# Production_SmartMic_V01.net
KiCad netlist of a schematic drawn in EAGLE
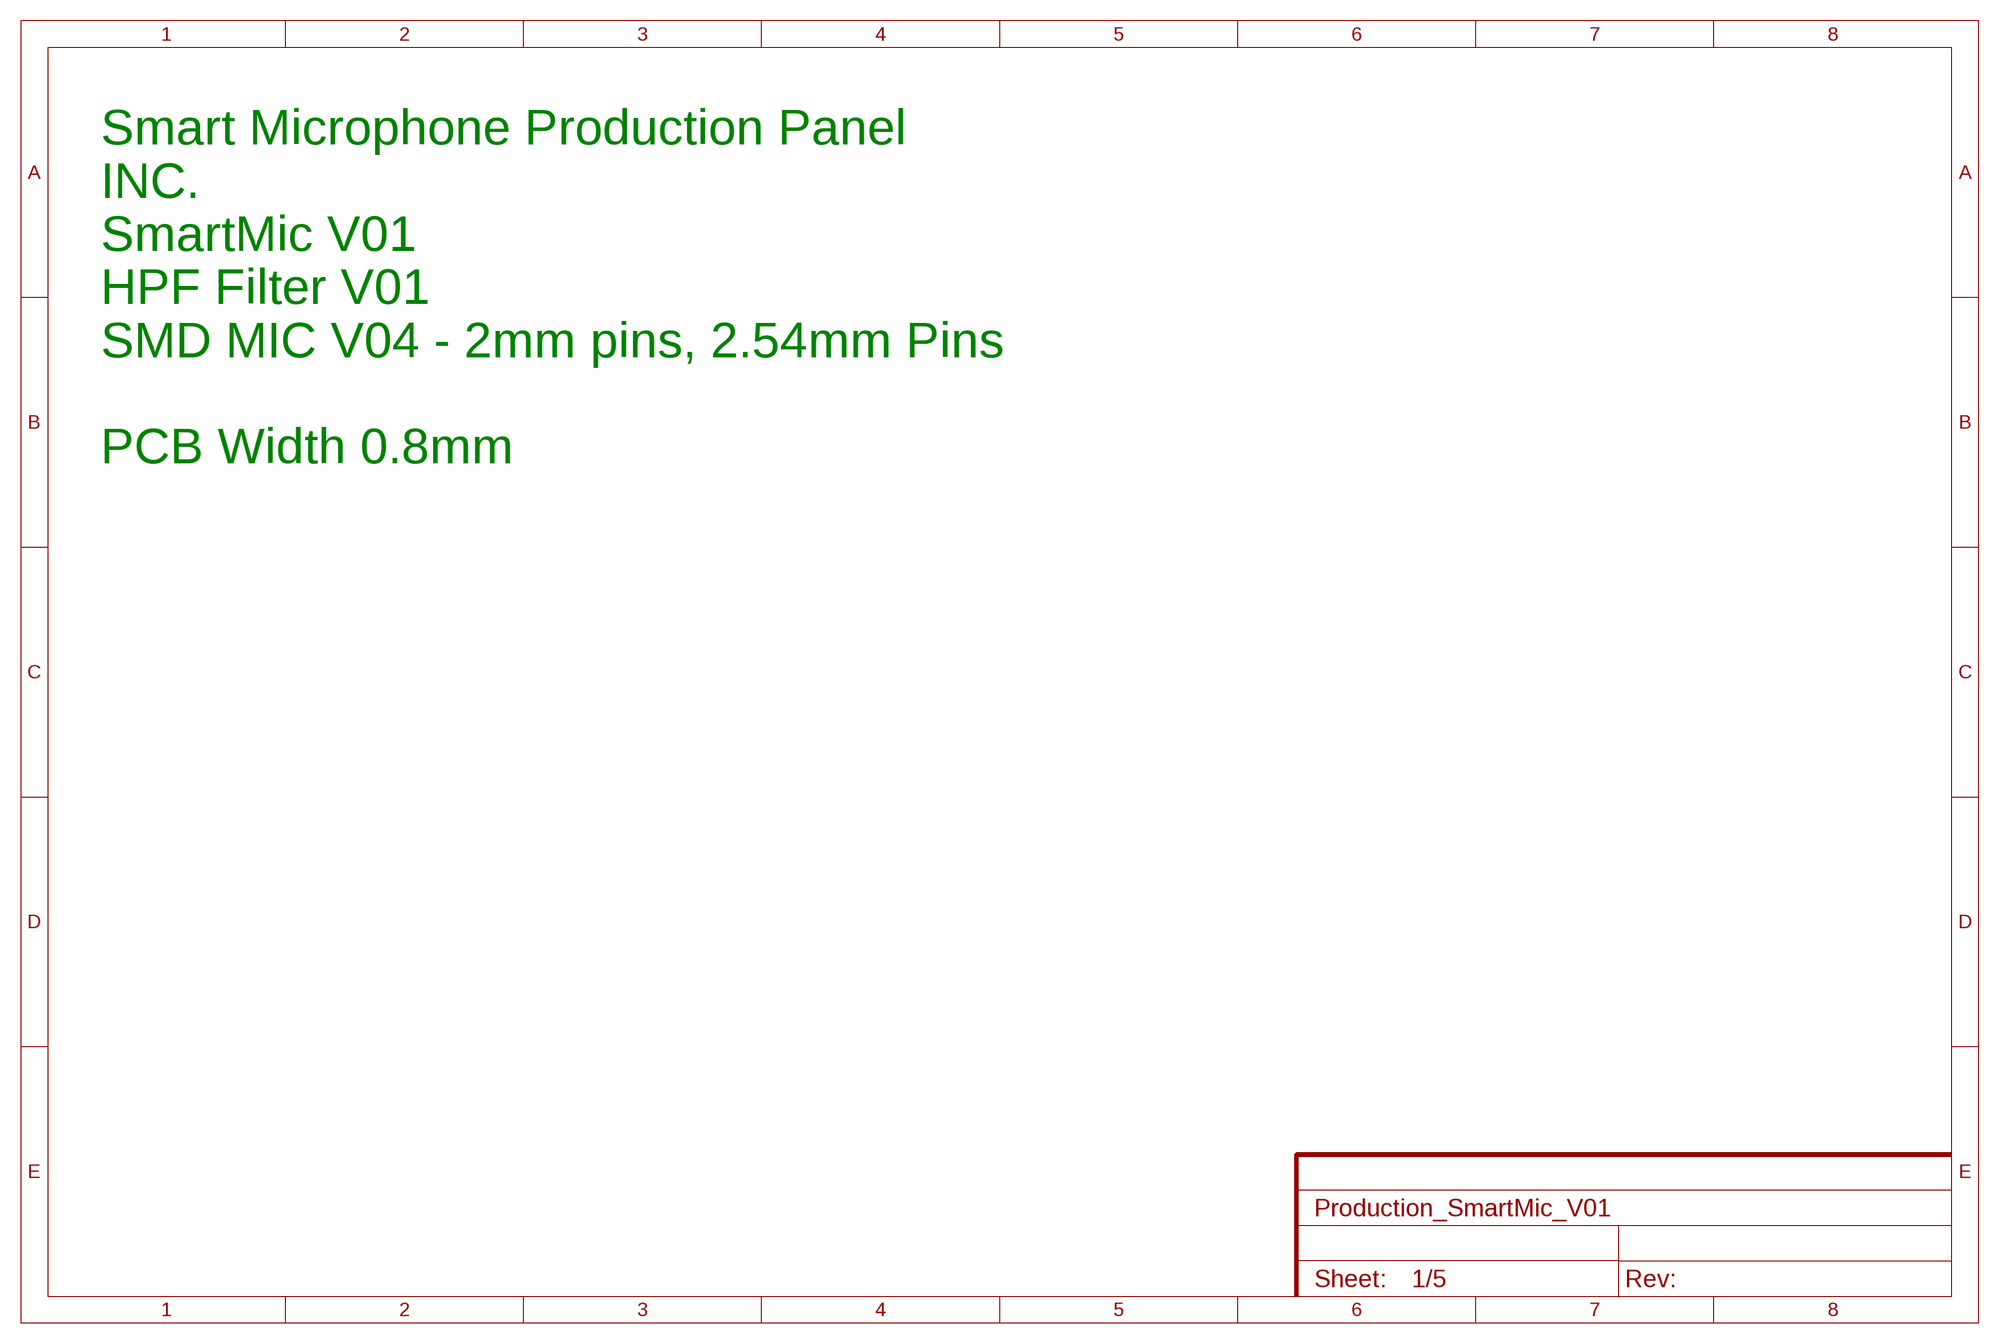
[diagram p0: schematic, sheet 1]
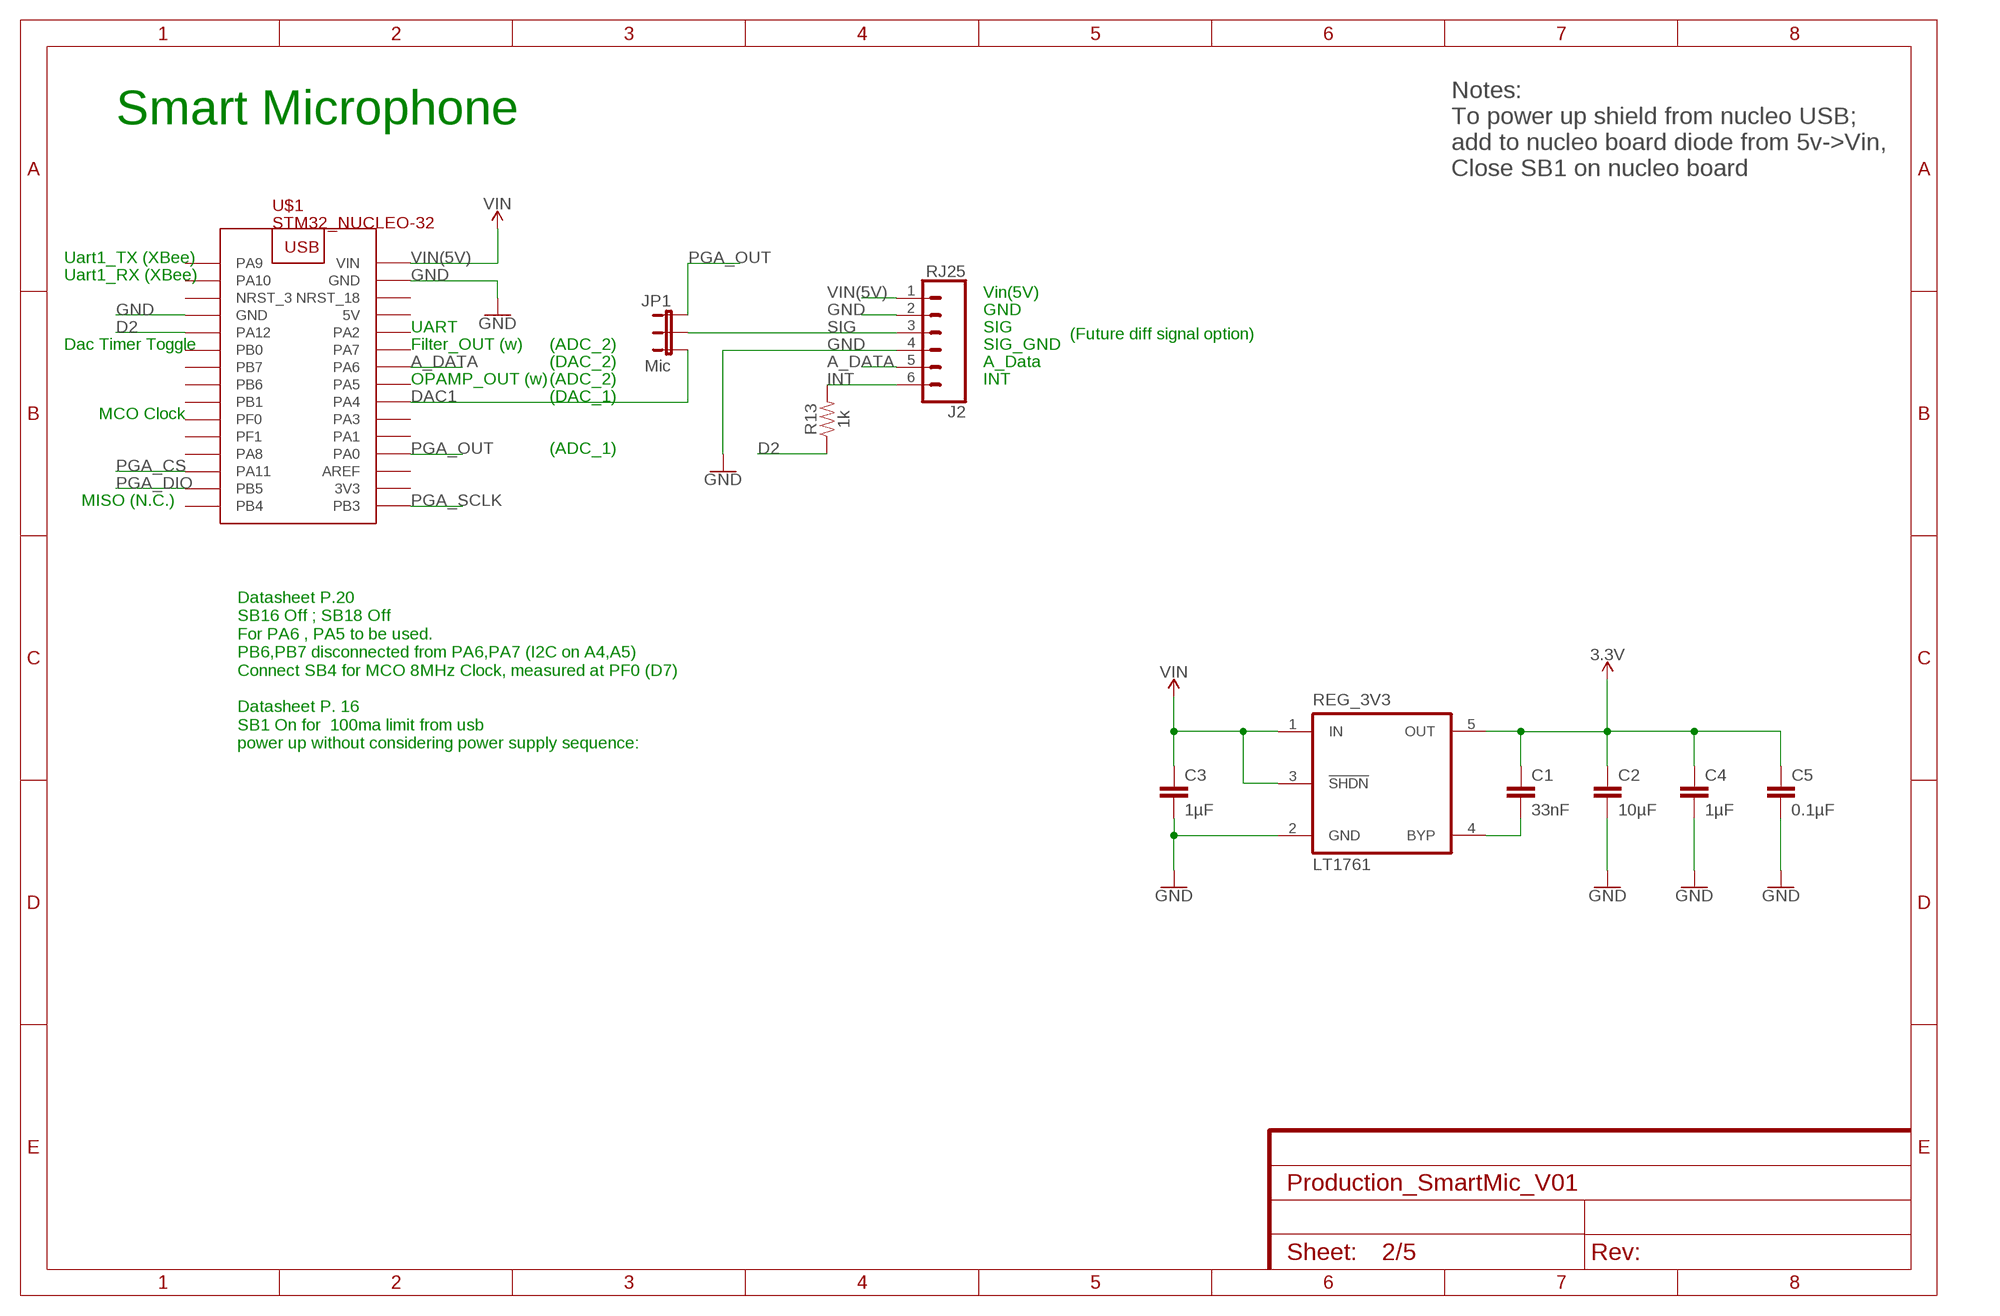
[diagram p1: schematic, sheet 2]
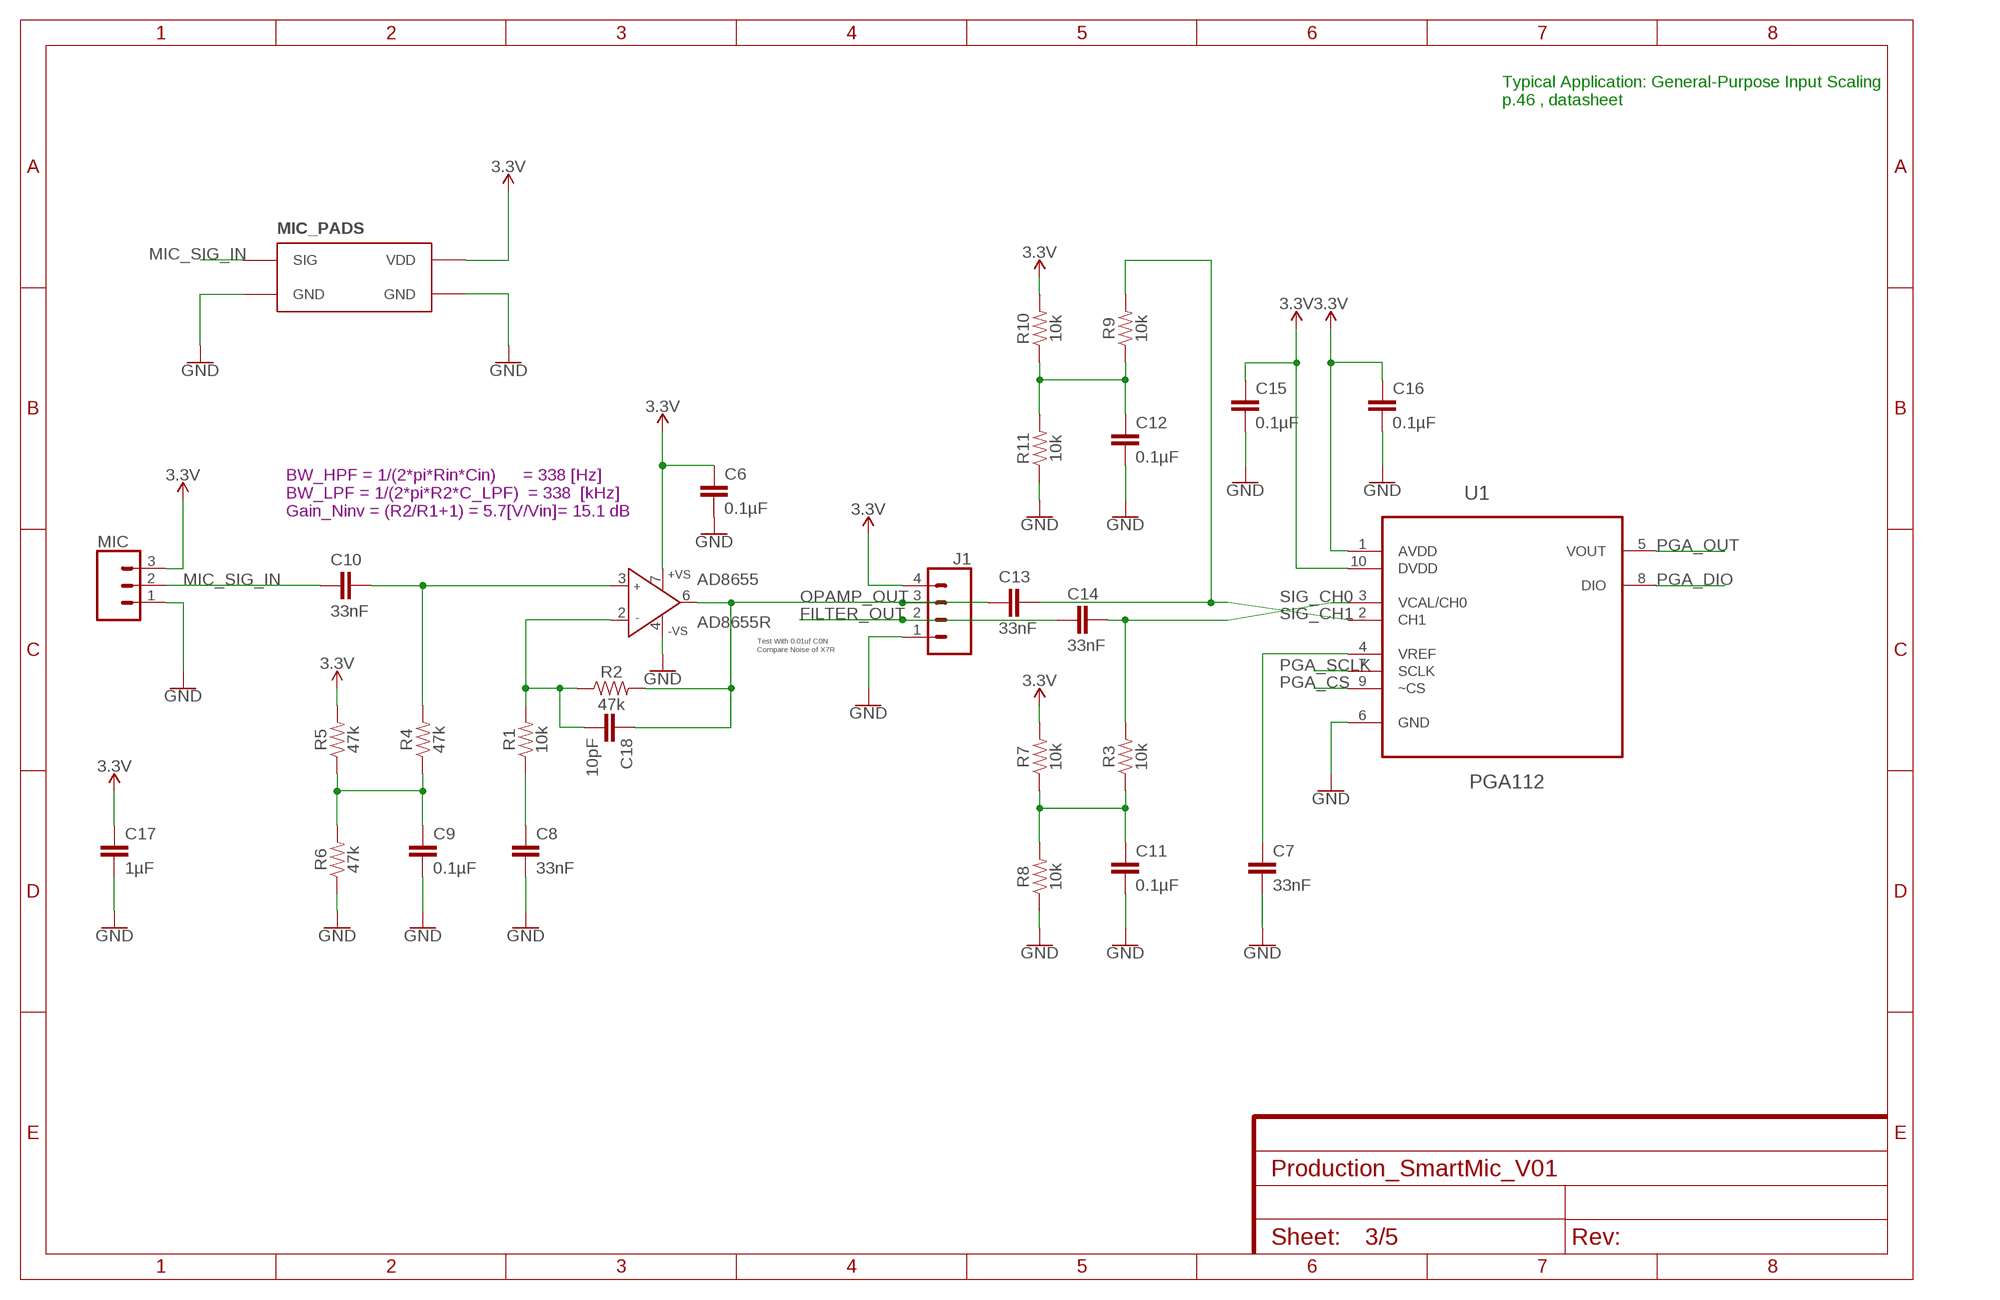
[diagram p2: schematic, sheet 3]
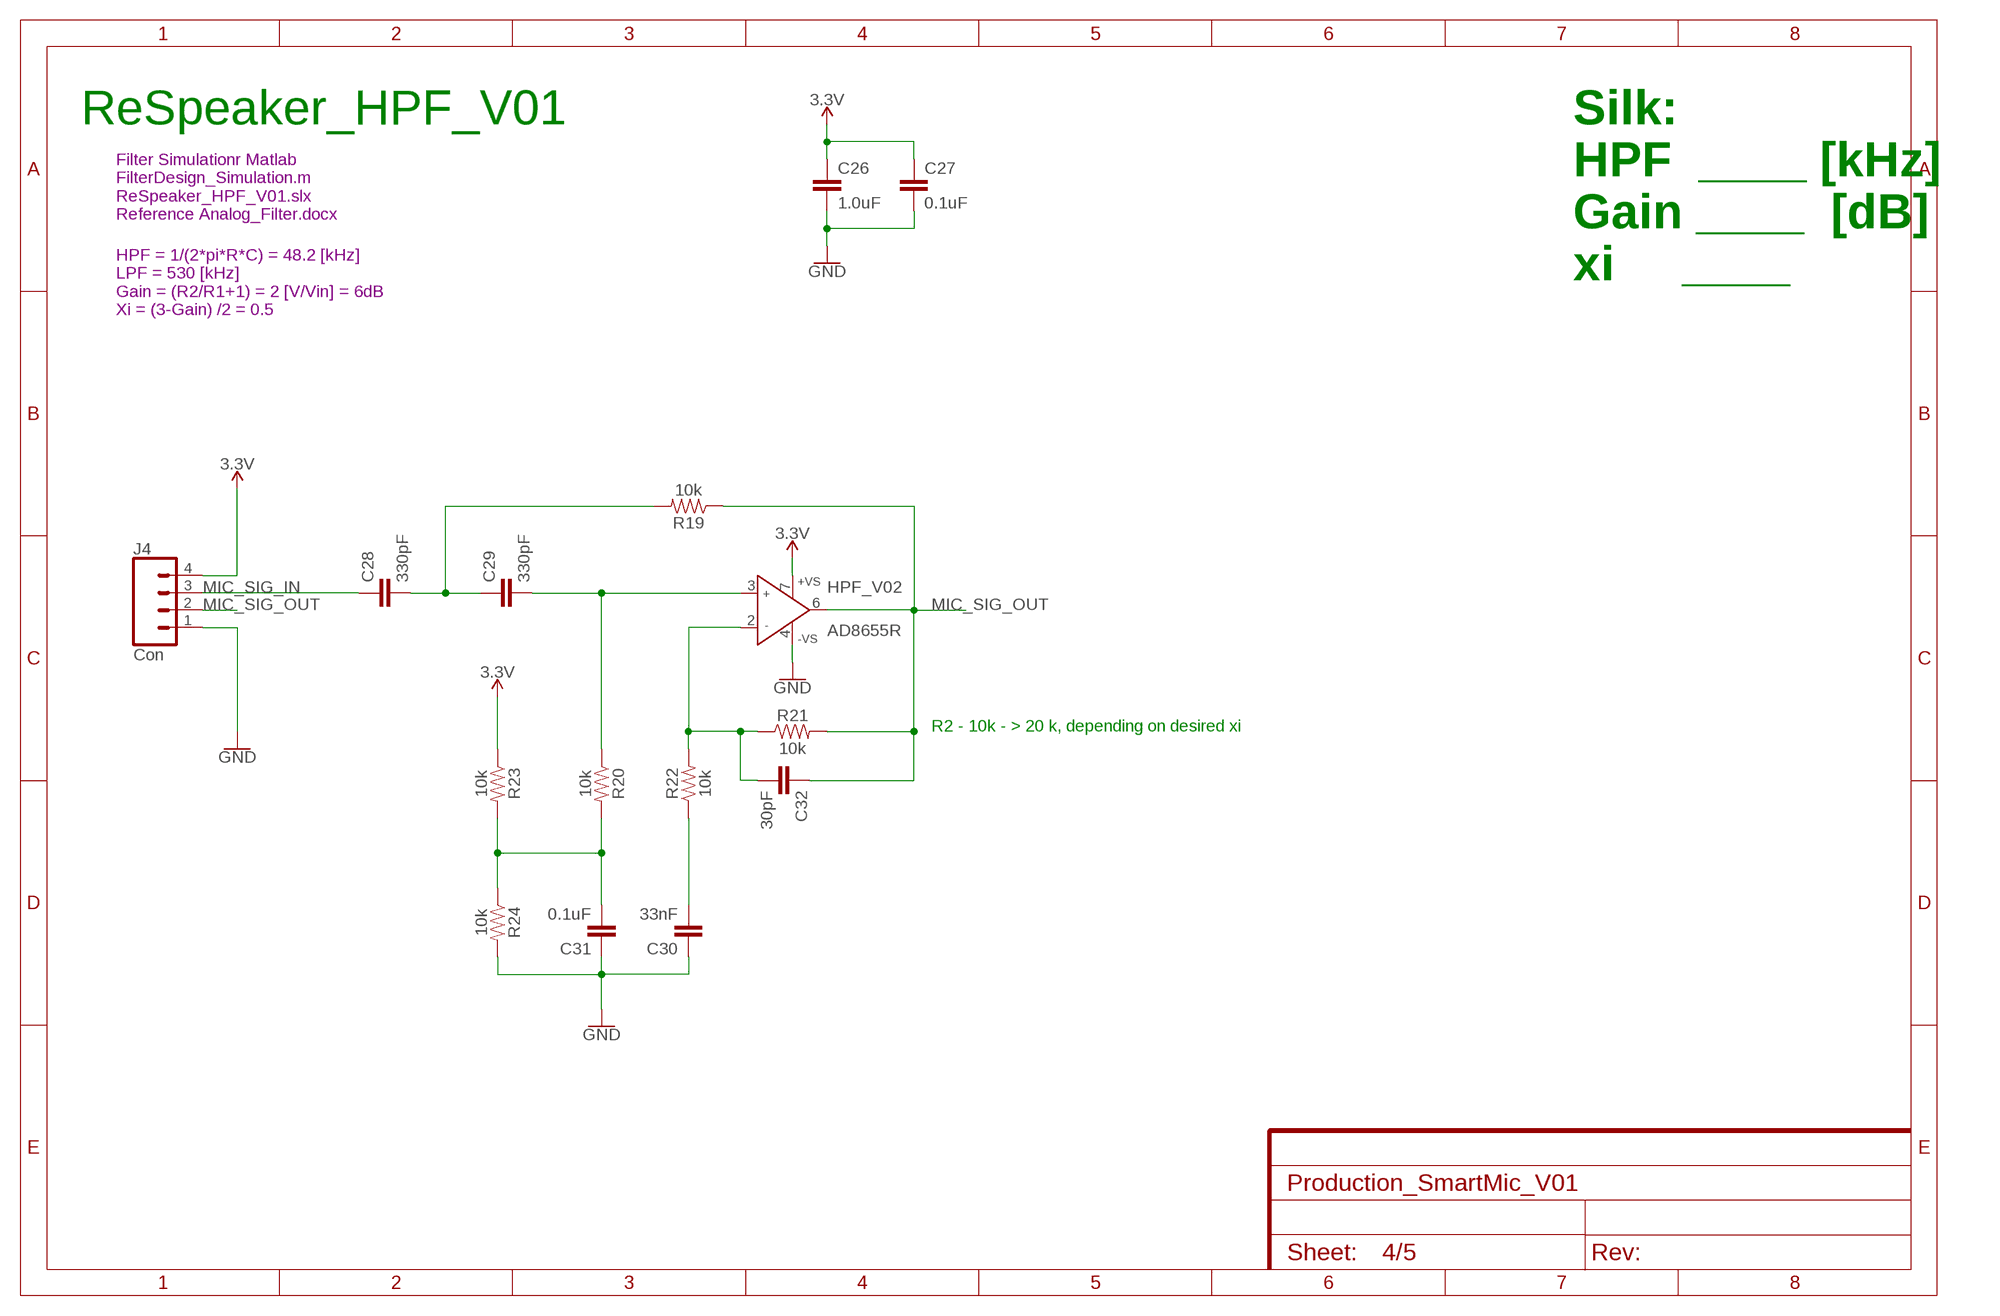
[diagram p3: schematic, sheet 4]
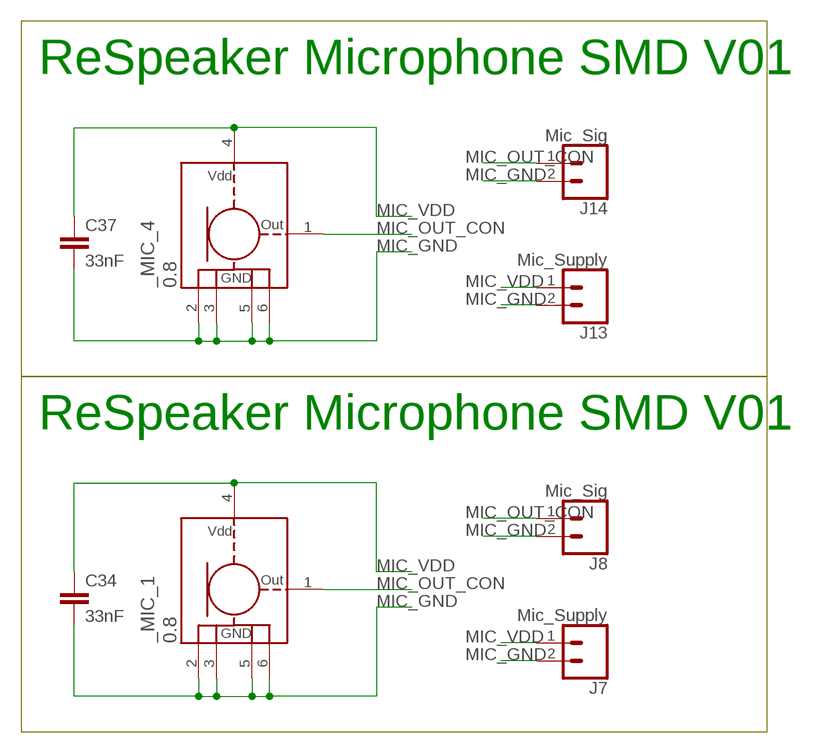
[diagram p4: schematic, sheet 5]

(export (version "E")
  (design (tool "Eeschema 10.0.6"))
  (components
    (comp (ref "C1")
      (value "33nF")
      (footprint "eagle-import:0805")
      (libsource (lib "eagle-import") (part "0.33UF/330NF-0805-50V-10%"))
    )
    (comp (ref "C2")
      (value "10µF")
      (footprint "eagle-import:0805")
      (libsource (lib "eagle-import") (part "0.33UF/330NF-0805-50V-10%"))
    )
    (comp (ref "C3")
      (value "1µF")
      (footprint "eagle-import:0805")
      (libsource (lib "eagle-import") (part "0.33UF/330NF-0805-50V-10%"))
    )
    (comp (ref "C4")
      (value "1µF")
      (footprint "eagle-import:0805")
      (libsource (lib "eagle-import") (part "0.33UF/330NF-0805-50V-10%"))
    )
    (comp (ref "C5")
      (value "0.1µF")
      (footprint "eagle-import:0805")
      (libsource (lib "eagle-import") (part "0.33UF/330NF-0805-50V-10%"))
    )
    (comp (ref "J2")
      (value "RJ25")
      (footprint "eagle-import:RJ11-6")
      (libsource (lib "eagle-import") (part "RJ11-6"))
    )
    (comp (ref "JP1")
      (value "Mic")
      (footprint "eagle-import:1X03")
      (libsource (lib "eagle-import") (part "JUMPER-3PTH"))
    )
    (comp (ref "R13")
      (value "1k")
      (footprint "eagle-import:0805")
      (libsource (lib "eagle-import") (part "RESISTOR0805"))
    )
    (comp (ref "REG_3V3")
      (value "LT1761")
      (footprint "eagle-import:SOT23-5")
      (libsource (lib "eagle-import") (part "LT1761"))
    )
    (comp (ref "U$1")
      (value "STM32_NUCLEO-32")
      (footprint "eagle-import:STM32_NUCLEO-32")
      (libsource (lib "eagle-import") (part "STM32_NUCLEO-32"))
    )
    (comp (ref "C26")
      (value "1.0uF")
      (footprint "eagle-import:0805")
      (libsource (lib "eagle-import") (part "1.0UF-0805-25V-10%"))
    )
    (comp (ref "C27")
      (value "0.1uF")
      (footprint "eagle-import:0805")
      (libsource (lib "eagle-import") (part "1.0UF-0805-25V-10%"))
    )
    (comp (ref "C28")
      (value "330pF")
      (footprint "eagle-import:0805")
      (libsource (lib "eagle-import") (part "1.0UF-0805-25V-10%"))
    )
    (comp (ref "C29")
      (value "330pF")
      (footprint "eagle-import:0805")
      (libsource (lib "eagle-import") (part "1.0UF-0805-25V-10%"))
    )
    (comp (ref "C30")
      (value "33nF")
      (footprint "eagle-import:0805")
      (libsource (lib "eagle-import") (part "1.0UF-0805-25V-10%"))
    )
    (comp (ref "C31")
      (value "0.1uF")
      (footprint "eagle-import:0805")
      (libsource (lib "eagle-import") (part "1.0UF-0805-25V-10%"))
    )
    (comp (ref "C32")
      (value "30pF")
      (footprint "eagle-import:0805")
      (libsource (lib "eagle-import") (part "1.0UF-0805-25V-10%"))
    )
    (comp (ref "HPF_V02")
      (value "AD8655R")
      (footprint "eagle-import:SO8")
      (fields (field (name "MF") "ALTERA CORPORATION") (field (name "MPN") "AD8655ARMZ-REEL"))
      (libsource (lib "eagle-import") (part "AD8655R"))
    )
    (comp (ref "J4")
      (value "Con")
      (footprint "eagle-import:1X04")
      (libsource (lib "eagle-import") (part "CONN_04"))
    )
    (comp (ref "R19")
      (value "10k")
      (footprint "eagle-import:0805")
      (libsource (lib "eagle-import") (part "RESISTOR0805"))
    )
    (comp (ref "R20")
      (value "10k")
      (footprint "eagle-import:0805")
      (libsource (lib "eagle-import") (part "RESISTOR0805"))
    )
    (comp (ref "R21")
      (value "10k")
      (footprint "eagle-import:0805")
      (libsource (lib "eagle-import") (part "RESISTOR0805"))
    )
    (comp (ref "R22")
      (value "10k")
      (footprint "eagle-import:0805")
      (libsource (lib "eagle-import") (part "RESISTOR0805"))
    )
    (comp (ref "R23")
      (value "10k")
      (footprint "eagle-import:0805")
      (libsource (lib "eagle-import") (part "RESISTOR0805"))
    )
    (comp (ref "R24")
      (value "10k")
      (footprint "eagle-import:0805")
      (libsource (lib "eagle-import") (part "RESISTOR0805"))
    )
    (comp (ref "C34")
      (value "33nF")
      (footprint "eagle-import:0805")
      (libsource (lib "eagle-import") (part "1.0UF-0805-25V-10%"))
    )
    (comp (ref "C37")
      (value "33nF")
      (footprint "eagle-import:0805")
      (libsource (lib "eagle-import") (part "1.0UF-0805-25V-10%"))
    )
    (comp (ref "J7")
      (value "Mic_Supply")
      (footprint "eagle-import:1X02_2.0MM")
      (libsource (lib "eagle-import") (part "CONN_021X02_2MM"))
    )
    (comp (ref "J8")
      (value "Mic_Sig")
      (footprint "eagle-import:1X02_2.0MM")
      (libsource (lib "eagle-import") (part "CONN_021X02_2MM"))
    )
    (comp (ref "J13")
      (value "Mic_Supply")
      (footprint "eagle-import:1X02")
      (libsource (lib "eagle-import") (part "SparkFun-Connectors_CONN_02"))
    )
    (comp (ref "J14")
      (value "Mic_Sig")
      (footprint "eagle-import:1X02")
      (libsource (lib "eagle-import") (part "SparkFun-Connectors_CONN_02"))
    )
    (comp (ref "_MIC_1")
      (value "0.8")
      (footprint "eagle-import:SPU0410LR5H-QB_0.8")
      (libsource (lib "eagle-import") (part "SPU0410LR5H-QBSPU0410LR5H-QB_0.8"))
    )
    (comp (ref "_MIC_4")
      (value "0.8")
      (footprint "eagle-import:SPU0410LR5H-QB_0.8")
      (libsource (lib "eagle-import") (part "SPU0410LR5H-QBSPU0410LR5H-QB_0.8"))
    )
    (comp (ref "AD8655")
      (value "AD8655R")
      (footprint "eagle-import:SO8")
      (fields (field (name "MF") "ALTERA CORPORATION") (field (name "MPN") "AD8655ARMZ-REEL"))
      (libsource (lib "eagle-import") (part "AD8655R"))
    )
    (comp (ref "C6")
      (value "0.1µF")
      (footprint "eagle-import:0805")
      (libsource (lib "eagle-import") (part "0.33UF/330NF-0805-50V-10%"))
    )
    (comp (ref "C7")
      (value "33nF")
      (footprint "eagle-import:0805")
      (libsource (lib "eagle-import") (part "0.33UF/330NF-0805-50V-10%"))
    )
    (comp (ref "C8")
      (value "33nF")
      (footprint "eagle-import:0805")
      (libsource (lib "eagle-import") (part "0.33UF/330NF-0805-50V-10%"))
    )
    (comp (ref "C9")
      (value "0.1µF")
      (footprint "eagle-import:0805")
      (libsource (lib "eagle-import") (part "0.33UF/330NF-0805-50V-10%"))
    )
    (comp (ref "C10")
      (value "33nF")
      (footprint "eagle-import:0805")
      (libsource (lib "eagle-import") (part "0.33UF/330NF-0805-50V-10%"))
    )
    (comp (ref "C11")
      (value "0.1µF")
      (footprint "eagle-import:0805")
      (libsource (lib "eagle-import") (part "0.33UF/330NF-0805-50V-10%"))
    )
    (comp (ref "C12")
      (value "0.1µF")
      (footprint "eagle-import:0805")
      (libsource (lib "eagle-import") (part "0.33UF/330NF-0805-50V-10%"))
    )
    (comp (ref "C13")
      (value "33nF")
      (footprint "eagle-import:0805")
      (libsource (lib "eagle-import") (part "0.33UF/330NF-0805-50V-10%"))
    )
    (comp (ref "C14")
      (value "33nF")
      (footprint "eagle-import:0805")
      (libsource (lib "eagle-import") (part "0.33UF/330NF-0805-50V-10%"))
    )
    (comp (ref "C15")
      (value "0.1µF")
      (footprint "eagle-import:0805")
      (libsource (lib "eagle-import") (part "0.33UF/330NF-0805-50V-10%"))
    )
    (comp (ref "C16")
      (value "0.1µF")
      (footprint "eagle-import:0805")
      (libsource (lib "eagle-import") (part "0.33UF/330NF-0805-50V-10%"))
    )
    (comp (ref "C17")
      (value "1µF")
      (footprint "eagle-import:0805")
      (libsource (lib "eagle-import") (part "0.33UF/330NF-0805-50V-10%"))
    )
    (comp (ref "C18")
      (value "10pF")
      (footprint "eagle-import:0805")
      (libsource (lib "eagle-import") (part "0.33UF/330NF-0805-50V-10%"))
    )
    (comp (ref "J1")
      (value "CONN_04")
      (footprint "eagle-import:1X04")
      (libsource (lib "eagle-import") (part "CONN_04"))
    )
    (comp (ref "MIC")
      (value "CONN_03")
      (footprint "eagle-import:1X03")
      (libsource (lib "eagle-import") (part "CONN_03"))
    )
    (comp (ref "R1")
      (value "10k")
      (footprint "eagle-import:0805")
      (libsource (lib "eagle-import") (part "RESISTOR0805"))
    )
    (comp (ref "R2")
      (value "47k")
      (footprint "eagle-import:0805")
      (libsource (lib "eagle-import") (part "RESISTOR0805"))
    )
    (comp (ref "R3")
      (value "10k")
      (footprint "eagle-import:0805")
      (libsource (lib "eagle-import") (part "RESISTOR0805"))
    )
    (comp (ref "R4")
      (value "47k")
      (footprint "eagle-import:0805")
      (libsource (lib "eagle-import") (part "RESISTOR0805"))
    )
    (comp (ref "R5")
      (value "47k")
      (footprint "eagle-import:0805")
      (libsource (lib "eagle-import") (part "RESISTOR0805"))
    )
    (comp (ref "R6")
      (value "47k")
      (footprint "eagle-import:0805")
      (libsource (lib "eagle-import") (part "RESISTOR0805"))
    )
    (comp (ref "R7")
      (value "10k")
      (footprint "eagle-import:0805")
      (libsource (lib "eagle-import") (part "RESISTOR0805"))
    )
    (comp (ref "R8")
      (value "10k")
      (footprint "eagle-import:0805")
      (libsource (lib "eagle-import") (part "RESISTOR0805"))
    )
    (comp (ref "R9")
      (value "10k")
      (footprint "eagle-import:0805")
      (libsource (lib "eagle-import") (part "RESISTOR0805"))
    )
    (comp (ref "R10")
      (value "10k")
      (footprint "eagle-import:0805")
      (libsource (lib "eagle-import") (part "RESISTOR0805"))
    )
    (comp (ref "R11")
      (value "10k")
      (footprint "eagle-import:0805")
      (libsource (lib "eagle-import") (part "RESISTOR0805"))
    )
    (comp (ref "U$2")
      (value "MIC_PADS")
      (footprint "eagle-import:MIC_PADS")
      (libsource (lib "eagle-import") (part "MIC_PADS"))
    )
    (comp (ref "U1")
      (value "PGA112")
      (footprint "eagle-import:SOP50P490X110-10N")
      (fields (field (name "MPN") "PGA113AIDGST"))
      (libsource (lib "eagle-import") (part "PGA113AIDGST"))
    )
  )
  (nets
    (net (code "1") (name "3.3V") (class "Default")
      (node (ref "AD8655") (pin "7") (pinfunction "+VS_7") (pintype "input"))
      (node (ref "C1") (pin "1") (pinfunction "1_1") (pintype "passive"))
      (node (ref "C15") (pin "1") (pinfunction "1_1") (pintype "passive"))
      (node (ref "C16") (pin "1") (pinfunction "1_1") (pintype "passive"))
      (node (ref "C17") (pin "1") (pinfunction "1_1") (pintype "passive"))
      (node (ref "C2") (pin "1") (pinfunction "1_1") (pintype "passive"))
      (node (ref "C26") (pin "1") (pinfunction "1_1") (pintype "passive"))
      (node (ref "C27") (pin "1") (pinfunction "1_1") (pintype "passive"))
      (node (ref "C4") (pin "1") (pinfunction "1_1") (pintype "passive"))
      (node (ref "C5") (pin "1") (pinfunction "1_1") (pintype "passive"))
      (node (ref "C6") (pin "1") (pinfunction "1_1") (pintype "passive"))
      (node (ref "HPF_V02") (pin "7") (pinfunction "+VS_7") (pintype "input"))
      (node (ref "J1") (pin "4") (pinfunction "4_4") (pintype "passive"))
      (node (ref "J4") (pin "4") (pinfunction "4_4") (pintype "passive"))
      (node (ref "MIC") (pin "3") (pinfunction "3_3") (pintype "passive"))
      (node (ref "R10") (pin "2") (pinfunction "2_2") (pintype "passive"))
      (node (ref "R23") (pin "1") (pinfunction "1_1") (pintype "passive"))
      (node (ref "R5") (pin "2") (pinfunction "2_2") (pintype "passive"))
      (node (ref "R7") (pin "2") (pinfunction "2_2") (pintype "passive"))
      (node (ref "REG_3V3") (pin "5") (pinfunction "OUT_5") (pintype "bidirectional"))
      (node (ref "U$2") (pin "VDD") (pinfunction "VDD_VDD") (pintype "bidirectional"))
      (node (ref "U1") (pin "1") (pinfunction "AVDD_1") (pintype "power_in"))
      (node (ref "U1") (pin "10") (pinfunction "DVDD_10") (pintype "power_in"))
    )
    (net (code "2") (name "3V3") (class "Default")
      (node (ref "U$1") (pin "3V3") (pinfunction "3V3_3V3") (pintype "power_in"))
    )
    (net (code "3") (name "5V") (class "Default")
      (node (ref "U$1") (pin "5V") (pinfunction "5V_5V") (pintype "power_in"))
    )
    (net (code "4") (name "A_DATA") (class "Default")
      (node (ref "J2") (pin "5") (pinfunction "5_5") (pintype "passive"))
      (node (ref "U$1") (pin "PA6") (pinfunction "PA6_PA6") (pintype "bidirectional"))
    )
    (net (code "5") (name "D2") (class "Default")
      (node (ref "R13") (pin "1") (pinfunction "1_1") (pintype "passive"))
      (node (ref "U$1") (pin "PA12") (pinfunction "PA12_PA12") (pintype "bidirectional"))
    )
    (net (code "6") (name "DAC1") (class "Default")
      (node (ref "JP1") (pin "3") (pinfunction "3_3") (pintype "passive"))
      (node (ref "U$1") (pin "PA4") (pinfunction "PA4_PA4") (pintype "bidirectional"))
    )
    (net (code "7") (name "FILTER_OUT") (class "Default")
      (node (ref "C14") (pin "2") (pinfunction "2_2") (pintype "passive"))
      (node (ref "J1") (pin "2") (pinfunction "2_2") (pintype "passive"))
    )
    (net (code "8") (name "GND") (class "Default")
      (node (ref "AD8655") (pin "4") (pinfunction "-VS_4") (pintype "input"))
      (node (ref "C11") (pin "2") (pinfunction "2_2") (pintype "passive"))
      (node (ref "C12") (pin "2") (pinfunction "2_2") (pintype "passive"))
      (node (ref "C15") (pin "2") (pinfunction "2_2") (pintype "passive"))
      (node (ref "C16") (pin "2") (pinfunction "2_2") (pintype "passive"))
      (node (ref "C17") (pin "2") (pinfunction "2_2") (pintype "passive"))
      (node (ref "C2") (pin "2") (pinfunction "2_2") (pintype "passive"))
      (node (ref "C26") (pin "2") (pinfunction "2_2") (pintype "passive"))
      (node (ref "C27") (pin "2") (pinfunction "2_2") (pintype "passive"))
      (node (ref "C3") (pin "2") (pinfunction "2_2") (pintype "passive"))
      (node (ref "C30") (pin "1") (pinfunction "1_1") (pintype "passive"))
      (node (ref "C31") (pin "1") (pinfunction "1_1") (pintype "passive"))
      (node (ref "C4") (pin "2") (pinfunction "2_2") (pintype "passive"))
      (node (ref "C5") (pin "2") (pinfunction "2_2") (pintype "passive"))
      (node (ref "C6") (pin "2") (pinfunction "2_2") (pintype "passive"))
      (node (ref "C7") (pin "2") (pinfunction "2_2") (pintype "passive"))
      (node (ref "C8") (pin "2") (pinfunction "2_2") (pintype "passive"))
      (node (ref "C9") (pin "2") (pinfunction "2_2") (pintype "passive"))
      (node (ref "HPF_V02") (pin "4") (pinfunction "-VS_4") (pintype "input"))
      (node (ref "J1") (pin "1") (pinfunction "1_1") (pintype "passive"))
      (node (ref "J2") (pin "2") (pinfunction "2_2") (pintype "passive"))
      (node (ref "J2") (pin "4") (pinfunction "4_4") (pintype "passive"))
      (node (ref "J4") (pin "1") (pinfunction "1_1") (pintype "passive"))
      (node (ref "MIC") (pin "1") (pinfunction "1_1") (pintype "passive"))
      (node (ref "R11") (pin "1") (pinfunction "1_1") (pintype "passive"))
      (node (ref "R24") (pin "2") (pinfunction "2_2") (pintype "passive"))
      (node (ref "R6") (pin "1") (pinfunction "1_1") (pintype "passive"))
      (node (ref "R8") (pin "1") (pinfunction "1_1") (pintype "passive"))
      (node (ref "REG_3V3") (pin "2") (pinfunction "GND_2") (pintype "bidirectional"))
      (node (ref "U$1") (pin "GND@17") (pinfunction "GND_GND@17") (pintype "power_in"))
      (node (ref "U$1") (pin "GND@4") (pinfunction "GND_GND@4") (pintype "power_in"))
      (node (ref "U$2") (pin "GND$2") (pinfunction "GND_GND$2") (pintype "bidirectional"))
      (node (ref "U$2") (pin "GND$4") (pinfunction "GND_GND$4") (pintype "bidirectional"))
      (node (ref "U1") (pin "6") (pinfunction "GND_6") (pintype "passive"))
    )
    (net (code "9") (name "INT") (class "Default")
      (node (ref "J2") (pin "6") (pinfunction "6_6") (pintype "passive"))
      (node (ref "R13") (pin "2") (pinfunction "2_2") (pintype "passive"))
    )
    (net (code "10") (name "MIC_GND") (class "Default")
      (node (ref "C34") (pin "2") (pinfunction "2_2") (pintype "passive"))
      (node (ref "C37") (pin "2") (pinfunction "2_2") (pintype "passive"))
      (node (ref "J13") (pin "2") (pinfunction "2_2") (pintype "passive"))
      (node (ref "J14") (pin "2") (pinfunction "2_2") (pintype "passive"))
      (node (ref "J7") (pin "2") (pinfunction "2_2") (pintype "passive"))
      (node (ref "J8") (pin "2") (pinfunction "2_2") (pintype "passive"))
      (node (ref "_MIC_1") (pin "2") (pinfunction "GND_2") (pintype "bidirectional"))
      (node (ref "_MIC_1") (pin "3") (pinfunction "GND_3") (pintype "bidirectional"))
      (node (ref "_MIC_1") (pin "5") (pinfunction "GND_5") (pintype "bidirectional"))
      (node (ref "_MIC_1") (pin "6") (pinfunction "GND_6") (pintype "bidirectional"))
      (node (ref "_MIC_4") (pin "2") (pinfunction "GND_2") (pintype "bidirectional"))
      (node (ref "_MIC_4") (pin "3") (pinfunction "GND_3") (pintype "bidirectional"))
      (node (ref "_MIC_4") (pin "5") (pinfunction "GND_5") (pintype "bidirectional"))
      (node (ref "_MIC_4") (pin "6") (pinfunction "GND_6") (pintype "bidirectional"))
    )
    (net (code "11") (name "MIC_OUT_CON") (class "Default")
      (node (ref "J14") (pin "1") (pinfunction "1_1") (pintype "passive"))
      (node (ref "J8") (pin "1") (pinfunction "1_1") (pintype "passive"))
      (node (ref "_MIC_1") (pin "1") (pinfunction "OUT_1") (pintype "bidirectional"))
      (node (ref "_MIC_4") (pin "1") (pinfunction "OUT_1") (pintype "bidirectional"))
    )
    (net (code "12") (name "MIC_SIG_IN") (class "Default")
      (node (ref "C10") (pin "2") (pinfunction "2_2") (pintype "passive"))
      (node (ref "C28") (pin "1") (pinfunction "1_1") (pintype "passive"))
      (node (ref "J4") (pin "3") (pinfunction "3_3") (pintype "passive"))
      (node (ref "MIC") (pin "2") (pinfunction "2_2") (pintype "passive"))
      (node (ref "U$2") (pin "SIG") (pinfunction "SIG_SIG") (pintype "bidirectional"))
    )
    (net (code "13") (name "MIC_SIG_OUT") (class "Default")
      (node (ref "C32") (pin "1") (pinfunction "1_1") (pintype "passive"))
      (node (ref "HPF_V02") (pin "6") (pinfunction "OUT_6") (pintype "output"))
      (node (ref "J4") (pin "2") (pinfunction "2_2") (pintype "passive"))
      (node (ref "R19") (pin "1") (pinfunction "1_1") (pintype "passive"))
      (node (ref "R21") (pin "2") (pinfunction "2_2") (pintype "passive"))
    )
    (net (code "14") (name "MIC_VDD") (class "Default")
      (node (ref "C34") (pin "1") (pinfunction "1_1") (pintype "passive"))
      (node (ref "C37") (pin "1") (pinfunction "1_1") (pintype "passive"))
      (node (ref "J13") (pin "1") (pinfunction "1_1") (pintype "passive"))
      (node (ref "J7") (pin "1") (pinfunction "1_1") (pintype "passive"))
      (node (ref "_MIC_1") (pin "4") (pinfunction "VDD_4") (pintype "bidirectional"))
      (node (ref "_MIC_4") (pin "4") (pinfunction "VDD_4") (pintype "bidirectional"))
    )
    (net (code "15") (name "Net-(AD8655-IN+)") (class "Default")
      (node (ref "AD8655") (pin "3") (pinfunction "IN+_3") (pintype "input"))
      (node (ref "C10") (pin "1") (pinfunction "1_1") (pintype "passive"))
      (node (ref "R4") (pin "2") (pinfunction "2_2") (pintype "passive"))
    )
    (net (code "16") (name "Net-(AD8655-IN-)") (class "Default")
      (node (ref "AD8655") (pin "2") (pinfunction "IN-_2") (pintype "input"))
      (node (ref "C18") (pin "2") (pinfunction "2_2") (pintype "passive"))
      (node (ref "R1") (pin "2") (pinfunction "2_2") (pintype "passive"))
      (node (ref "R2") (pin "1") (pinfunction "1_1") (pintype "passive"))
    )
    (net (code "17") (name "Net-(C8-Pad1)") (class "Default")
      (node (ref "C8") (pin "1") (pinfunction "1_1") (pintype "passive"))
      (node (ref "R1") (pin "1") (pinfunction "1_1") (pintype "passive"))
    )
    (net (code "18") (name "Net-(C9-Pad1)") (class "Default")
      (node (ref "C9") (pin "1") (pinfunction "1_1") (pintype "passive"))
      (node (ref "R4") (pin "1") (pinfunction "1_1") (pintype "passive"))
      (node (ref "R5") (pin "1") (pinfunction "1_1") (pintype "passive"))
      (node (ref "R6") (pin "2") (pinfunction "2_2") (pintype "passive"))
    )
    (net (code "19") (name "Net-(C11-Pad1)") (class "Default")
      (node (ref "C11") (pin "1") (pinfunction "1_1") (pintype "passive"))
      (node (ref "R3") (pin "1") (pinfunction "1_1") (pintype "passive"))
      (node (ref "R7") (pin "1") (pinfunction "1_1") (pintype "passive"))
      (node (ref "R8") (pin "2") (pinfunction "2_2") (pintype "passive"))
    )
    (net (code "20") (name "Net-(C12-Pad1)") (class "Default")
      (node (ref "C12") (pin "1") (pinfunction "1_1") (pintype "passive"))
      (node (ref "R10") (pin "1") (pinfunction "1_1") (pintype "passive"))
      (node (ref "R11") (pin "2") (pinfunction "2_2") (pintype "passive"))
      (node (ref "R9") (pin "1") (pinfunction "1_1") (pintype "passive"))
    )
    (net (code "21") (name "Net-(C28-Pad2)") (class "Default")
      (node (ref "C28") (pin "2") (pinfunction "2_2") (pintype "passive"))
      (node (ref "C29") (pin "1") (pinfunction "1_1") (pintype "passive"))
      (node (ref "R19") (pin "2") (pinfunction "2_2") (pintype "passive"))
    )
    (net (code "22") (name "Net-(C30-Pad2)") (class "Default")
      (node (ref "C30") (pin "2") (pinfunction "2_2") (pintype "passive"))
      (node (ref "R22") (pin "1") (pinfunction "1_1") (pintype "passive"))
    )
    (net (code "23") (name "Net-(C31-Pad2)") (class "Default")
      (node (ref "C31") (pin "2") (pinfunction "2_2") (pintype "passive"))
      (node (ref "R20") (pin "2") (pinfunction "2_2") (pintype "passive"))
      (node (ref "R23") (pin "2") (pinfunction "2_2") (pintype "passive"))
      (node (ref "R24") (pin "1") (pinfunction "1_1") (pintype "passive"))
    )
    (net (code "24") (name "Net-(HPF_V02-IN+)") (class "Default")
      (node (ref "C29") (pin "2") (pinfunction "2_2") (pintype "passive"))
      (node (ref "HPF_V02") (pin "3") (pinfunction "IN+_3") (pintype "input"))
      (node (ref "R20") (pin "1") (pinfunction "1_1") (pintype "passive"))
    )
    (net (code "25") (name "Net-(HPF_V02-IN-)") (class "Default")
      (node (ref "C32") (pin "2") (pinfunction "2_2") (pintype "passive"))
      (node (ref "HPF_V02") (pin "2") (pinfunction "IN-_2") (pintype "input"))
      (node (ref "R21") (pin "1") (pinfunction "1_1") (pintype "passive"))
      (node (ref "R22") (pin "2") (pinfunction "2_2") (pintype "passive"))
    )
    (net (code "26") (name "Net-(REG_3V3-BYP)") (class "Default")
      (node (ref "C1") (pin "2") (pinfunction "2_2") (pintype "passive"))
      (node (ref "REG_3V3") (pin "4") (pinfunction "BYP_4") (pintype "bidirectional"))
    )
    (net (code "27") (name "Net-(U1-VREF)") (class "Default")
      (node (ref "C7") (pin "1") (pinfunction "1_1") (pintype "passive"))
      (node (ref "U1") (pin "4") (pinfunction "VREF_4") (pintype "input"))
    )
    (net (code "28") (name "OPAMP_OUT") (class "Default")
      (node (ref "AD8655") (pin "6") (pinfunction "OUT_6") (pintype "output"))
      (node (ref "C13") (pin "2") (pinfunction "2_2") (pintype "passive"))
      (node (ref "C18") (pin "1") (pinfunction "1_1") (pintype "passive"))
      (node (ref "J1") (pin "3") (pinfunction "3_3") (pintype "passive"))
      (node (ref "R2") (pin "2") (pinfunction "2_2") (pintype "passive"))
    )
    (net (code "29") (name "PGA_CS") (class "Default")
      (node (ref "U$1") (pin "PA11") (pinfunction "PA11_PA11") (pintype "bidirectional"))
      (node (ref "U1") (pin "9") (pinfunction "~{CS}_9") (pintype "input"))
    )
    (net (code "30") (name "PGA_DIO") (class "Default")
      (node (ref "U$1") (pin "PB5") (pinfunction "PB5_PB5") (pintype "bidirectional"))
      (node (ref "U1") (pin "8") (pinfunction "DIO_8") (pintype "bidirectional"))
    )
    (net (code "31") (name "PGA_OUT") (class "Default")
      (node (ref "JP1") (pin "1") (pinfunction "1_1") (pintype "passive"))
      (node (ref "U$1") (pin "PA0") (pinfunction "PA0_PA0") (pintype "bidirectional"))
      (node (ref "U1") (pin "5") (pinfunction "VOUT_5") (pintype "output"))
    )
    (net (code "32") (name "PGA_SCLK") (class "Default")
      (node (ref "U$1") (pin "PB3") (pinfunction "PB3_PB3") (pintype "bidirectional"))
      (node (ref "U1") (pin "7") (pinfunction "SCLK_7") (pintype "input"))
    )
    (net (code "33") (name "SIG") (class "Default")
      (node (ref "J2") (pin "3") (pinfunction "3_3") (pintype "passive"))
      (node (ref "JP1") (pin "2") (pinfunction "2_2") (pintype "passive"))
    )
    (net (code "34") (name "SIG_CH0") (class "Default")
      (node (ref "C13") (pin "1") (pinfunction "1_1") (pintype "passive"))
      (node (ref "R9") (pin "2") (pinfunction "2_2") (pintype "passive"))
      (node (ref "U1") (pin "2") (pinfunction "CH1_2") (pintype "input"))
    )
    (net (code "35") (name "SIG_CH1") (class "Default")
      (node (ref "C14") (pin "1") (pinfunction "1_1") (pintype "passive"))
      (node (ref "R3") (pin "2") (pinfunction "2_2") (pintype "passive"))
      (node (ref "U1") (pin "3") (pinfunction "VCAL/CH0_3") (pintype "input"))
    )
    (net (code "36") (name "VIN(5V)") (class "Default")
      (node (ref "C3") (pin "1") (pinfunction "1_1") (pintype "passive"))
      (node (ref "J2") (pin "1") (pinfunction "1_1") (pintype "passive"))
      (node (ref "REG_3V3") (pin "1") (pinfunction "IN_1") (pintype "bidirectional"))
      (node (ref "REG_3V3") (pin "3") (pinfunction "~{SHDN}_3") (pintype "bidirectional"))
      (node (ref "U$1") (pin "VIN") (pinfunction "VIN_VIN") (pintype "power_in"))
    )
    (net (code "37") (name "unconnected-(U$1-PadAREF)") (class "Default")
      (node (ref "U$1") (pin "AREF") (pinfunction "AREF_AREF") (pintype "bidirectional"))
    )
    (net (code "38") (name "unconnected-(U$1-PadNRST_3)") (class "Default")
      (node (ref "U$1") (pin "NRST_3") (pinfunction "NRST_3_NRST_3") (pintype "bidirectional"))
    )
    (net (code "39") (name "unconnected-(U$1-PadNRST_18)") (class "Default")
      (node (ref "U$1") (pin "NRST_18") (pinfunction "NRST_18_NRST_18") (pintype "bidirectional"))
    )
    (net (code "40") (name "unconnected-(U$1-PadPA1)") (class "Default")
      (node (ref "U$1") (pin "PA1") (pinfunction "PA1_PA1") (pintype "bidirectional"))
    )
    (net (code "41") (name "unconnected-(U$1-PadPA2)") (class "Default")
      (node (ref "U$1") (pin "PA2") (pinfunction "PA2_PA2") (pintype "bidirectional"))
    )
    (net (code "42") (name "unconnected-(U$1-PadPA3)") (class "Default")
      (node (ref "U$1") (pin "PA3") (pinfunction "PA3_PA3") (pintype "bidirectional"))
    )
    (net (code "43") (name "unconnected-(U$1-PadPA5)") (class "Default")
      (node (ref "U$1") (pin "PA5") (pinfunction "PA5_PA5") (pintype "bidirectional"))
    )
    (net (code "44") (name "unconnected-(U$1-PadPA7)") (class "Default")
      (node (ref "U$1") (pin "PA7") (pinfunction "PA7_PA7") (pintype "bidirectional"))
    )
    (net (code "45") (name "unconnected-(U$1-PadPA8)") (class "Default")
      (node (ref "U$1") (pin "PA8") (pinfunction "PA8_PA8") (pintype "bidirectional"))
    )
    (net (code "46") (name "unconnected-(U$1-PadPA9)") (class "Default")
      (node (ref "U$1") (pin "PA9") (pinfunction "PA9_PA9") (pintype "bidirectional"))
    )
    (net (code "47") (name "unconnected-(U$1-PadPA10)") (class "Default")
      (node (ref "U$1") (pin "PA10") (pinfunction "PA10_PA10") (pintype "bidirectional"))
    )
    (net (code "48") (name "unconnected-(U$1-PadPB0)") (class "Default")
      (node (ref "U$1") (pin "PB0") (pinfunction "PB0_PB0") (pintype "bidirectional"))
    )
    (net (code "49") (name "unconnected-(U$1-PadPB1)") (class "Default")
      (node (ref "U$1") (pin "PB1") (pinfunction "PB1_PB1") (pintype "bidirectional"))
    )
    (net (code "50") (name "unconnected-(U$1-PadPB4)") (class "Default")
      (node (ref "U$1") (pin "PB4") (pinfunction "PB4_PB4") (pintype "bidirectional"))
    )
    (net (code "51") (name "unconnected-(U$1-PadPB6)") (class "Default")
      (node (ref "U$1") (pin "PB6") (pinfunction "PB6_PB6") (pintype "bidirectional"))
    )
    (net (code "52") (name "unconnected-(U$1-PadPB7)") (class "Default")
      (node (ref "U$1") (pin "PB7") (pinfunction "PB7_PB7") (pintype "bidirectional"))
    )
    (net (code "53") (name "unconnected-(U$1-PadPF0)") (class "Default")
      (node (ref "U$1") (pin "PF0") (pinfunction "PF0_PF0") (pintype "bidirectional"))
    )
    (net (code "54") (name "unconnected-(U$1-PadPF1)") (class "Default")
      (node (ref "U$1") (pin "PF1") (pinfunction "PF1_PF1") (pintype "bidirectional"))
    )
  )
)
